# LightSensorDigital.net
KiCad netlist of a schematic drawn in EAGLE
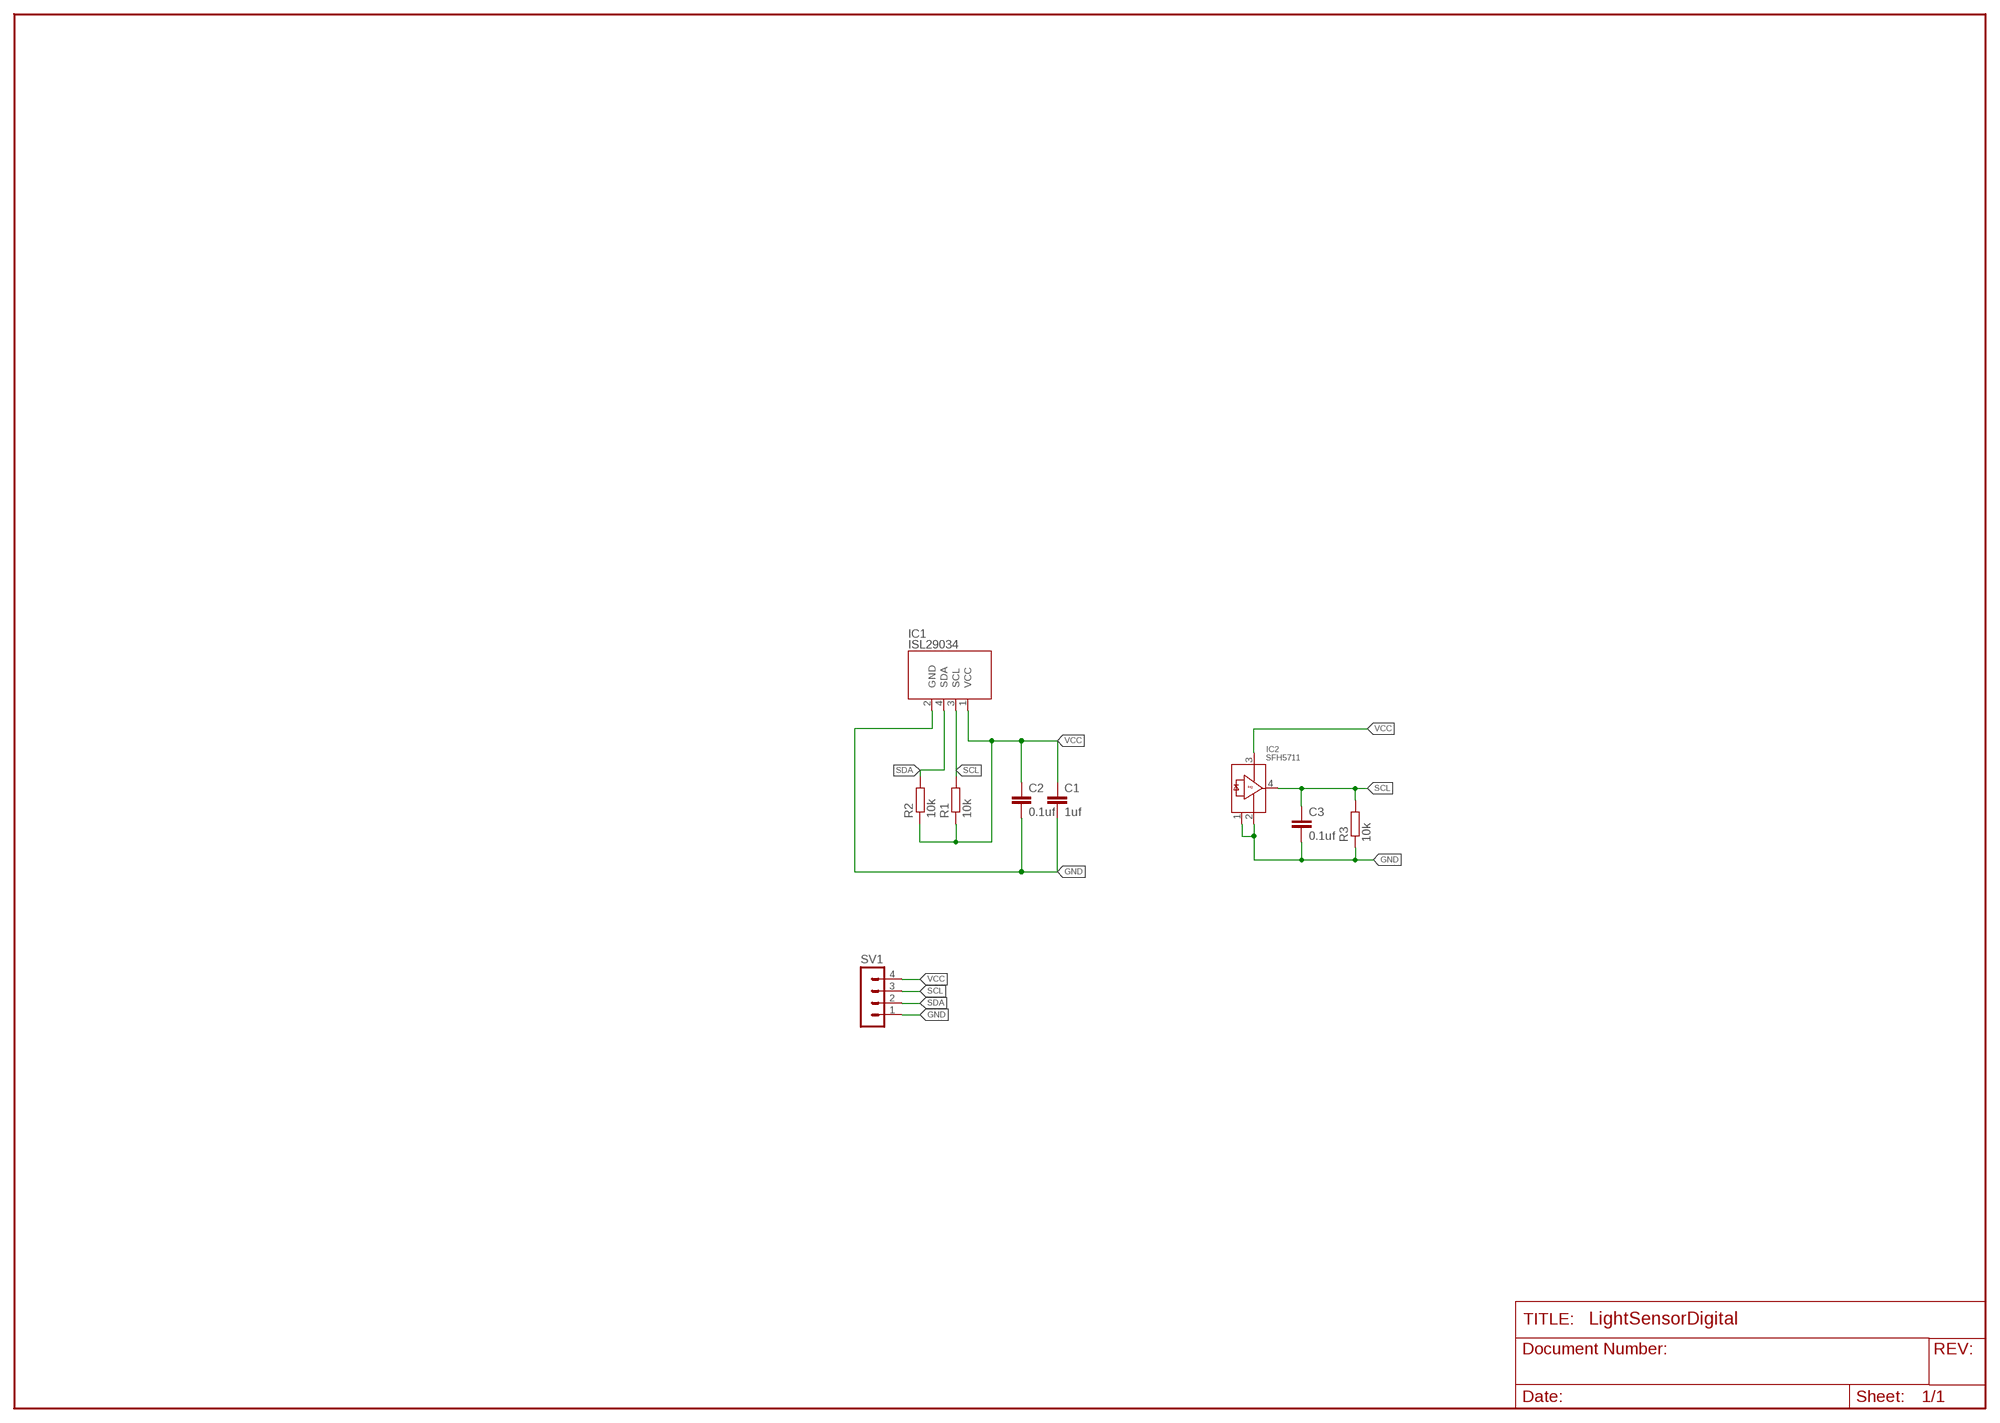
[diagram p0: schematic, sheet 1]

(export (version "E")
  (design (tool "Eeschema 10.0.6"))
  (components
    (comp (ref "C1")
      (value "1uf")
      (footprint "eagle-import:0603")
      (libsource (lib "eagle-import") (part "SMD_C0603"))
    )
    (comp (ref "C2")
      (value "0.1uf")
      (footprint "eagle-import:0603")
      (libsource (lib "eagle-import") (part "SMD_C0603"))
    )
    (comp (ref "C3")
      (value "0.1uf")
      (footprint "eagle-import:0603")
      (libsource (lib "eagle-import") (part "SMD_C0603"))
    )
    (comp (ref "IC1")
      (value "ISL29034")
      (footprint "eagle-import:ISL29034")
      (libsource (lib "eagle-import") (part "ISL29034"))
    )
    (comp (ref "IC2")
      (value "SFH5711")
      (footprint "eagle-import:SFH5711")
      (fields (field (name "MF") "OSRAM Opto"))
      (libsource (lib "eagle-import") (part "SFH5711"))
    )
    (comp (ref "R1")
      (value "10k")
      (footprint "eagle-import:0603")
      (libsource (lib "eagle-import") (part "SMD_R0603"))
    )
    (comp (ref "R2")
      (value "10k")
      (footprint "eagle-import:0603")
      (libsource (lib "eagle-import") (part "SMD_R0603"))
    )
    (comp (ref "R3")
      (value "10k")
      (footprint "eagle-import:0603")
      (libsource (lib "eagle-import") (part "SMD_R0603"))
    )
    (comp (ref "SV1")
      (value "MA04-1")
      (footprint "eagle-import:MA04-1")
      (libsource (lib "eagle-import") (part "MA04-1"))
    )
  )
  (nets
    (net (code "1") (name "GND") (class "Default")
      (node (ref "C1") (pin "2") (pinfunction "2_2") (pintype "passive"))
      (node (ref "C2") (pin "2") (pinfunction "2_2") (pintype "passive"))
      (node (ref "C3") (pin "2") (pinfunction "2_2") (pintype "passive"))
      (node (ref "IC1") (pin "2") (pinfunction "GND_2") (pintype "bidirectional"))
      (node (ref "IC2") (pin "1") (pinfunction "1_1") (pintype "bidirectional"))
      (node (ref "IC2") (pin "2") (pinfunction "2_2") (pintype "bidirectional"))
      (node (ref "R3") (pin "1") (pinfunction "1_1") (pintype "passive"))
      (node (ref "SV1") (pin "1") (pinfunction "1_1") (pintype "passive"))
    )
    (net (code "2") (name "SCL") (class "Default")
      (node (ref "C3") (pin "1") (pinfunction "1_1") (pintype "passive"))
      (node (ref "IC1") (pin "3") (pinfunction "SCL_3") (pintype "bidirectional"))
      (node (ref "IC2") (pin "4") (pinfunction "4_4") (pintype "bidirectional"))
      (node (ref "R1") (pin "2") (pinfunction "2_2") (pintype "passive"))
      (node (ref "R3") (pin "2") (pinfunction "2_2") (pintype "passive"))
      (node (ref "SV1") (pin "3") (pinfunction "3_3") (pintype "passive"))
    )
    (net (code "3") (name "SDA") (class "Default")
      (node (ref "IC1") (pin "4") (pinfunction "SDA_4") (pintype "bidirectional"))
      (node (ref "R2") (pin "2") (pinfunction "2_2") (pintype "passive"))
      (node (ref "SV1") (pin "2") (pinfunction "2_2") (pintype "passive"))
    )
    (net (code "4") (name "VCC") (class "Default")
      (node (ref "C1") (pin "1") (pinfunction "1_1") (pintype "passive"))
      (node (ref "C2") (pin "1") (pinfunction "1_1") (pintype "passive"))
      (node (ref "IC1") (pin "1") (pinfunction "VCC_1") (pintype "bidirectional"))
      (node (ref "IC2") (pin "3") (pinfunction "3_3") (pintype "bidirectional"))
      (node (ref "R1") (pin "1") (pinfunction "1_1") (pintype "passive"))
      (node (ref "R2") (pin "1") (pinfunction "1_1") (pintype "passive"))
      (node (ref "SV1") (pin "4") (pinfunction "4_4") (pintype "passive"))
    )
  )
)
